# DriverModuleWing.net
KiCad netlist of a schematic drawn in EAGLE
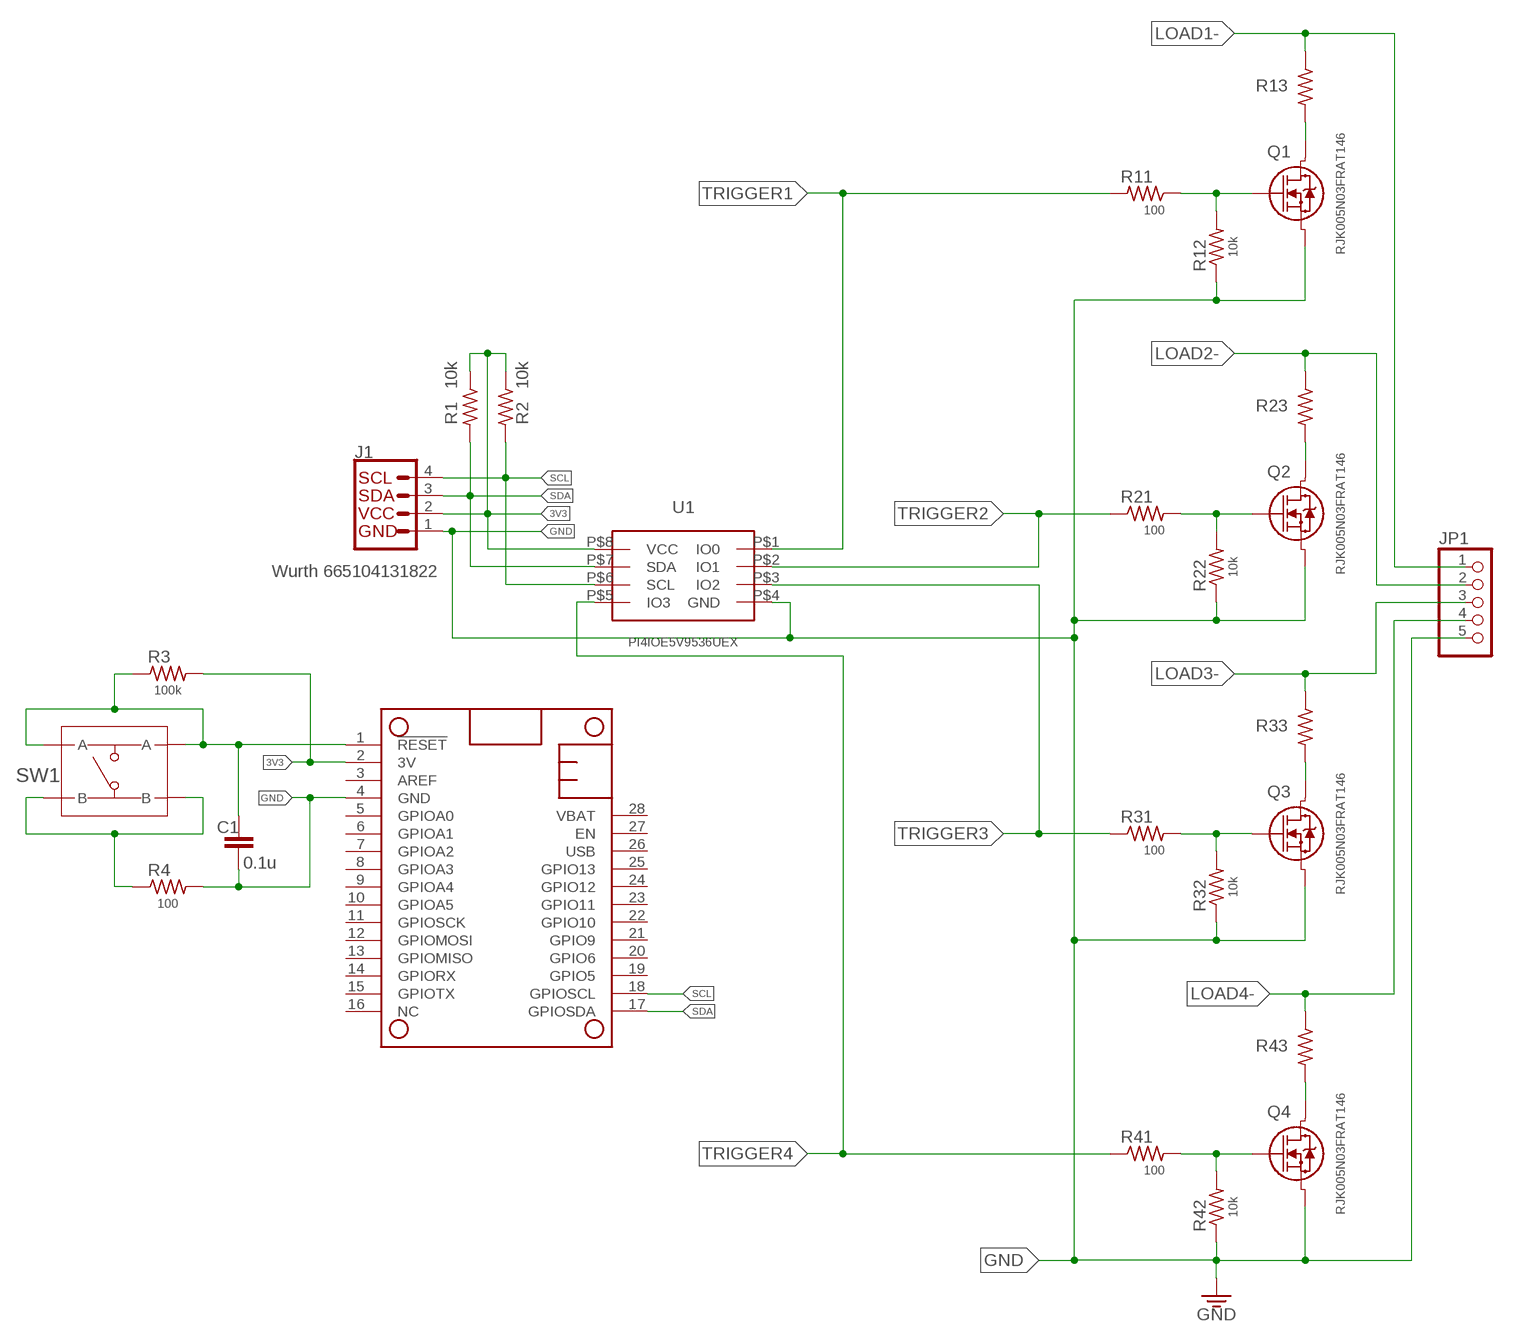
[diagram p0: schematic, sheet 1]

(export (version "E")
  (design (tool "Eeschema 10.0.6"))
  (components
    (comp (ref "C1")
      (value "0.1u")
      (footprint "eagle-import:SMD-0805")
      (libsource (lib "eagle-import") (part "C-SMD-0805"))
    )
    (comp (ref "J1")
      (value "Wurth 665104131822")
      (footprint "eagle-import:1X04_1MM_RA")
      (libsource (lib "eagle-import") (part "QWIIC_CONNECTORJS-1MM"))
    )
    (comp (ref "JP1")
      (value "HEADER-1X576MIL")
      (footprint "eagle-import:1X05_ROUND_76")
      (libsource (lib "eagle-import") (part "HEADER-1X576MIL"))
    )
    (comp (ref "MS1")
      (value "FEATHERWING_NODIM")
      (footprint "eagle-import:FEATHERWING_DIM")
      (libsource (lib "eagle-import") (part "FEATHERWING_NODIM"))
    )
    (comp (ref "Q1")
      (value "RJK005N03FRAT146")
      (footprint "eagle-import:TRANS_RHK003N_ROM-M")
      (fields (field (name "COPYRIGHT") "Copyright (C) 2022 Ultra Librarian. All rights reserved."))
      (libsource (lib "eagle-import") (part "RJK005N03FRAT146TRANS_RHK003N_ROM-M"))
    )
    (comp (ref "Q2")
      (value "RJK005N03FRAT146")
      (footprint "eagle-import:TRANS_RHK003N_ROM-M")
      (fields (field (name "COPYRIGHT") "Copyright (C) 2022 Ultra Librarian. All rights reserved."))
      (libsource (lib "eagle-import") (part "RJK005N03FRAT146TRANS_RHK003N_ROM-M"))
    )
    (comp (ref "Q3")
      (value "RJK005N03FRAT146")
      (footprint "eagle-import:TRANS_RHK003N_ROM-M")
      (fields (field (name "COPYRIGHT") "Copyright (C) 2022 Ultra Librarian. All rights reserved."))
      (libsource (lib "eagle-import") (part "RJK005N03FRAT146TRANS_RHK003N_ROM-M"))
    )
    (comp (ref "Q4")
      (value "RJK005N03FRAT146")
      (footprint "eagle-import:TRANS_RHK003N_ROM-M")
      (fields (field (name "COPYRIGHT") "Copyright (C) 2022 Ultra Librarian. All rights reserved."))
      (libsource (lib "eagle-import") (part "RJK005N03FRAT146TRANS_RHK003N_ROM-M"))
    )
    (comp (ref "R1")
      (value "10k")
      (footprint "eagle-import:R0603")
      (libsource (lib "eagle-import") (part "R-US_R0603"))
    )
    (comp (ref "R2")
      (value "10k")
      (footprint "eagle-import:R0603")
      (libsource (lib "eagle-import") (part "R-US_R0603"))
    )
    (comp (ref "R3")
      (value "100k")
      (footprint "eagle-import:R0603")
      (libsource (lib "eagle-import") (part "R-US_R0603"))
    )
    (comp (ref "R4")
      (value "100")
      (footprint "eagle-import:R0603")
      (libsource (lib "eagle-import") (part "R-US_R0603"))
    )
    (comp (ref "R11")
      (value "100")
      (footprint "eagle-import:R0603")
      (libsource (lib "eagle-import") (part "R-US_R0603"))
    )
    (comp (ref "R12")
      (value "10k")
      (footprint "eagle-import:R0603")
      (libsource (lib "eagle-import") (part "R-US_R0603"))
    )
    (comp (ref "R13")
      (value "R-US_R1206")
      (footprint "eagle-import:R1206")
      (libsource (lib "eagle-import") (part "R-US_R1206"))
    )
    (comp (ref "R21")
      (value "100")
      (footprint "eagle-import:R0603")
      (libsource (lib "eagle-import") (part "R-US_R0603"))
    )
    (comp (ref "R22")
      (value "10k")
      (footprint "eagle-import:R0603")
      (libsource (lib "eagle-import") (part "R-US_R0603"))
    )
    (comp (ref "R23")
      (value "R-US_R1206")
      (footprint "eagle-import:R1206")
      (libsource (lib "eagle-import") (part "R-US_R1206"))
    )
    (comp (ref "R31")
      (value "100")
      (footprint "eagle-import:R0603")
      (libsource (lib "eagle-import") (part "R-US_R0603"))
    )
    (comp (ref "R32")
      (value "10k")
      (footprint "eagle-import:R0603")
      (libsource (lib "eagle-import") (part "R-US_R0603"))
    )
    (comp (ref "R33")
      (value "R-US_R1206")
      (footprint "eagle-import:R1206")
      (libsource (lib "eagle-import") (part "R-US_R1206"))
    )
    (comp (ref "R41")
      (value "100")
      (footprint "eagle-import:R0603")
      (libsource (lib "eagle-import") (part "R-US_R0603"))
    )
    (comp (ref "R42")
      (value "10k")
      (footprint "eagle-import:R0603")
      (libsource (lib "eagle-import") (part "R-US_R0603"))
    )
    (comp (ref "R43")
      (value "R-US_R1206")
      (footprint "eagle-import:R1206")
      (libsource (lib "eagle-import") (part "R-US_R1206"))
    )
    (comp (ref "SW1")
      (value "PTS645SK43SMTR92LFS-PTS647-4.5")
      (footprint "eagle-import:SWITCH_CK_PTS647SN38SMTR2LFS")
      (libsource (lib "eagle-import") (part "PTS645SK43SMTR92LFS-PTS647-4.5"))
    )
    (comp (ref "U1")
      (value "PI4IOE5V9536UEX")
      (footprint "eagle-import:MSOP-8")
      (libsource (lib "eagle-import") (part "PI4IOE5V9536-UEX"))
    )
  )
  (nets
    (net (code "1") (name "/USB") (class "Default")
      (node (ref "MS1") (pin "26") (pinfunction "USB_26") (pintype "power_in"))
    )
    (net (code "2") (name "/VBAT") (class "Default")
      (node (ref "MS1") (pin "28") (pinfunction "VBAT_28") (pintype "power_in"))
    )
    (net (code "3") (name "3V3") (class "Default")
      (node (ref "J1") (pin "2") (pinfunction "VCC_2") (pintype "power_in"))
      (node (ref "MS1") (pin "2") (pinfunction "3V_2") (pintype "power_in"))
      (node (ref "R1") (pin "1") (pinfunction "1_1") (pintype "passive"))
      (node (ref "R2") (pin "1") (pinfunction "1_1") (pintype "passive"))
      (node (ref "R3") (pin "2") (pinfunction "2_2") (pintype "passive"))
      (node (ref "U1") (pin "P$8") (pinfunction "VCC_P$8") (pintype "bidirectional"))
    )
    (net (code "4") (name "GND") (class "Default")
      (node (ref "C1") (pin "P$2") (pinfunction "2_P$2") (pintype "passive"))
      (node (ref "J1") (pin "1") (pinfunction "GND_1") (pintype "power_in"))
      (node (ref "JP1") (pin "5") (pinfunction "5_5") (pintype "passive"))
      (node (ref "MS1") (pin "4") (pinfunction "GND_4") (pintype "power_in"))
      (node (ref "Q1") (pin "3") (pinfunction "3_3") (pintype "passive"))
      (node (ref "Q2") (pin "3") (pinfunction "3_3") (pintype "passive"))
      (node (ref "Q3") (pin "3") (pinfunction "3_3") (pintype "passive"))
      (node (ref "Q4") (pin "3") (pinfunction "3_3") (pintype "passive"))
      (node (ref "R12") (pin "1") (pinfunction "1_1") (pintype "passive"))
      (node (ref "R22") (pin "1") (pinfunction "1_1") (pintype "passive"))
      (node (ref "R32") (pin "1") (pinfunction "1_1") (pintype "passive"))
      (node (ref "R4") (pin "2") (pinfunction "2_2") (pintype "passive"))
      (node (ref "R42") (pin "1") (pinfunction "1_1") (pintype "passive"))
      (node (ref "U1") (pin "P$4") (pinfunction "GND_P$4") (pintype "bidirectional"))
    )
    (net (code "5") (name "LOAD1-") (class "Default")
      (node (ref "JP1") (pin "1") (pinfunction "1_1") (pintype "passive"))
      (node (ref "R13") (pin "1") (pinfunction "1_1") (pintype "passive"))
    )
    (net (code "6") (name "LOAD2-") (class "Default")
      (node (ref "JP1") (pin "2") (pinfunction "2_2") (pintype "passive"))
      (node (ref "R23") (pin "1") (pinfunction "1_1") (pintype "passive"))
    )
    (net (code "7") (name "LOAD3-") (class "Default")
      (node (ref "JP1") (pin "3") (pinfunction "3_3") (pintype "passive"))
      (node (ref "R33") (pin "1") (pinfunction "1_1") (pintype "passive"))
    )
    (net (code "8") (name "LOAD4-") (class "Default")
      (node (ref "JP1") (pin "4") (pinfunction "4_4") (pintype "passive"))
      (node (ref "R43") (pin "1") (pinfunction "1_1") (pintype "passive"))
    )
    (net (code "9") (name "Net-(C1-1)") (class "Default")
      (node (ref "C1") (pin "P$1") (pinfunction "1_P$1") (pintype "passive"))
      (node (ref "MS1") (pin "1") (pinfunction "~{RESET}_1") (pintype "input"))
      (node (ref "R3") (pin "1") (pinfunction "1_1") (pintype "passive"))
      (node (ref "SW1") (pin "1") (pinfunction "A_1") (pintype "passive"))
      (node (ref "SW1") (pin "2") (pinfunction "A_2") (pintype "passive"))
    )
    (net (code "10") (name "Net-(Q1-1)") (class "Default")
      (node (ref "Q1") (pin "2") (pinfunction "1_2") (pintype "passive"))
      (node (ref "R11") (pin "1") (pinfunction "1_1") (pintype "passive"))
      (node (ref "R12") (pin "2") (pinfunction "2_2") (pintype "passive"))
    )
    (net (code "11") (name "Net-(Q1-2)") (class "Default")
      (node (ref "Q1") (pin "1") (pinfunction "2_1") (pintype "passive"))
      (node (ref "R13") (pin "2") (pinfunction "2_2") (pintype "passive"))
    )
    (net (code "12") (name "Net-(Q2-1)") (class "Default")
      (node (ref "Q2") (pin "2") (pinfunction "1_2") (pintype "passive"))
      (node (ref "R21") (pin "2") (pinfunction "2_2") (pintype "passive"))
      (node (ref "R22") (pin "2") (pinfunction "2_2") (pintype "passive"))
    )
    (net (code "13") (name "Net-(Q2-2)") (class "Default")
      (node (ref "Q2") (pin "1") (pinfunction "2_1") (pintype "passive"))
      (node (ref "R23") (pin "2") (pinfunction "2_2") (pintype "passive"))
    )
    (net (code "14") (name "Net-(Q3-1)") (class "Default")
      (node (ref "Q3") (pin "2") (pinfunction "1_2") (pintype "passive"))
      (node (ref "R31") (pin "2") (pinfunction "2_2") (pintype "passive"))
      (node (ref "R32") (pin "2") (pinfunction "2_2") (pintype "passive"))
    )
    (net (code "15") (name "Net-(Q3-2)") (class "Default")
      (node (ref "Q3") (pin "1") (pinfunction "2_1") (pintype "passive"))
      (node (ref "R33") (pin "2") (pinfunction "2_2") (pintype "passive"))
    )
    (net (code "16") (name "Net-(Q4-1)") (class "Default")
      (node (ref "Q4") (pin "2") (pinfunction "1_2") (pintype "passive"))
      (node (ref "R41") (pin "2") (pinfunction "2_2") (pintype "passive"))
      (node (ref "R42") (pin "2") (pinfunction "2_2") (pintype "passive"))
    )
    (net (code "17") (name "Net-(Q4-2)") (class "Default")
      (node (ref "Q4") (pin "1") (pinfunction "2_1") (pintype "passive"))
      (node (ref "R43") (pin "2") (pinfunction "2_2") (pintype "passive"))
    )
    (net (code "18") (name "Net-(R4-Pad1)") (class "Default")
      (node (ref "R4") (pin "1") (pinfunction "1_1") (pintype "passive"))
      (node (ref "SW1") (pin "3") (pinfunction "B_3") (pintype "passive"))
      (node (ref "SW1") (pin "4") (pinfunction "B_4") (pintype "passive"))
    )
    (net (code "19") (name "SCL") (class "Default")
      (node (ref "J1") (pin "4") (pinfunction "SCL_4") (pintype "passive"))
      (node (ref "MS1") (pin "18") (pinfunction "GPIOSCL_18") (pintype "bidirectional"))
      (node (ref "R2") (pin "2") (pinfunction "2_2") (pintype "passive"))
      (node (ref "U1") (pin "P$6") (pinfunction "SCL_P$6") (pintype "bidirectional"))
    )
    (net (code "20") (name "SDA") (class "Default")
      (node (ref "J1") (pin "3") (pinfunction "SDA_3") (pintype "passive"))
      (node (ref "MS1") (pin "17") (pinfunction "GPIOSDA_17") (pintype "bidirectional"))
      (node (ref "R1") (pin "2") (pinfunction "2_2") (pintype "passive"))
      (node (ref "U1") (pin "P$7") (pinfunction "SDA_P$7") (pintype "bidirectional"))
    )
    (net (code "21") (name "TRIGGER1") (class "Default")
      (node (ref "R11") (pin "2") (pinfunction "2_2") (pintype "passive"))
      (node (ref "U1") (pin "P$1") (pinfunction "IO0_P$1") (pintype "bidirectional"))
    )
    (net (code "22") (name "TRIGGER2") (class "Default")
      (node (ref "R21") (pin "1") (pinfunction "1_1") (pintype "passive"))
      (node (ref "U1") (pin "P$2") (pinfunction "IO1_P$2") (pintype "bidirectional"))
    )
    (net (code "23") (name "TRIGGER3") (class "Default")
      (node (ref "R31") (pin "1") (pinfunction "1_1") (pintype "passive"))
      (node (ref "U1") (pin "P$3") (pinfunction "IO2_P$3") (pintype "bidirectional"))
    )
    (net (code "24") (name "TRIGGER4") (class "Default")
      (node (ref "R41") (pin "1") (pinfunction "1_1") (pintype "passive"))
      (node (ref "U1") (pin "P$5") (pinfunction "IO3_P$5") (pintype "bidirectional"))
    )
    (net (code "25") (name "unconnected-(MS1-AREF-Pad3)") (class "Default")
      (node (ref "MS1") (pin "3") (pinfunction "AREF_3") (pintype "passive"))
    )
    (net (code "26") (name "unconnected-(MS1-EN-Pad27)") (class "Default")
      (node (ref "MS1") (pin "27") (pinfunction "EN_27") (pintype "passive"))
    )
    (net (code "27") (name "unconnected-(MS1-GPIO5-Pad19)") (class "Default")
      (node (ref "MS1") (pin "19") (pinfunction "GPIO5_19") (pintype "bidirectional"))
    )
    (net (code "28") (name "unconnected-(MS1-GPIO6-Pad20)") (class "Default")
      (node (ref "MS1") (pin "20") (pinfunction "GPIO6_20") (pintype "bidirectional"))
    )
    (net (code "29") (name "unconnected-(MS1-GPIO9-Pad21)") (class "Default")
      (node (ref "MS1") (pin "21") (pinfunction "GPIO9_21") (pintype "bidirectional"))
    )
    (net (code "30") (name "unconnected-(MS1-GPIO10-Pad22)") (class "Default")
      (node (ref "MS1") (pin "22") (pinfunction "GPIO10_22") (pintype "bidirectional"))
    )
    (net (code "31") (name "unconnected-(MS1-GPIO11-Pad23)") (class "Default")
      (node (ref "MS1") (pin "23") (pinfunction "GPIO11_23") (pintype "bidirectional"))
    )
    (net (code "32") (name "unconnected-(MS1-GPIO12-Pad24)") (class "Default")
      (node (ref "MS1") (pin "24") (pinfunction "GPIO12_24") (pintype "bidirectional"))
    )
    (net (code "33") (name "unconnected-(MS1-GPIO13-Pad25)") (class "Default")
      (node (ref "MS1") (pin "25") (pinfunction "GPIO13_25") (pintype "bidirectional"))
    )
    (net (code "34") (name "unconnected-(MS1-GPIOA0-Pad5)") (class "Default")
      (node (ref "MS1") (pin "5") (pinfunction "GPIOA0_5") (pintype "bidirectional"))
    )
    (net (code "35") (name "unconnected-(MS1-GPIOA1-Pad6)") (class "Default")
      (node (ref "MS1") (pin "6") (pinfunction "GPIOA1_6") (pintype "bidirectional"))
    )
    (net (code "36") (name "unconnected-(MS1-GPIOA2-Pad7)") (class "Default")
      (node (ref "MS1") (pin "7") (pinfunction "GPIOA2_7") (pintype "bidirectional"))
    )
    (net (code "37") (name "unconnected-(MS1-GPIOA3-Pad8)") (class "Default")
      (node (ref "MS1") (pin "8") (pinfunction "GPIOA3_8") (pintype "bidirectional"))
    )
    (net (code "38") (name "unconnected-(MS1-GPIOA4-Pad9)") (class "Default")
      (node (ref "MS1") (pin "9") (pinfunction "GPIOA4_9") (pintype "bidirectional"))
    )
    (net (code "39") (name "unconnected-(MS1-GPIOA5-Pad10)") (class "Default")
      (node (ref "MS1") (pin "10") (pinfunction "GPIOA5_10") (pintype "bidirectional"))
    )
    (net (code "40") (name "unconnected-(MS1-GPIOMISO-Pad13)") (class "Default")
      (node (ref "MS1") (pin "13") (pinfunction "GPIOMISO_13") (pintype "bidirectional"))
    )
    (net (code "41") (name "unconnected-(MS1-GPIOMOSI-Pad12)") (class "Default")
      (node (ref "MS1") (pin "12") (pinfunction "GPIOMOSI_12") (pintype "bidirectional"))
    )
    (net (code "42") (name "unconnected-(MS1-GPIORX-Pad14)") (class "Default")
      (node (ref "MS1") (pin "14") (pinfunction "GPIORX_14") (pintype "bidirectional"))
    )
    (net (code "43") (name "unconnected-(MS1-GPIOSCK-Pad11)") (class "Default")
      (node (ref "MS1") (pin "11") (pinfunction "GPIOSCK_11") (pintype "bidirectional"))
    )
    (net (code "44") (name "unconnected-(MS1-GPIOTX-Pad15)") (class "Default")
      (node (ref "MS1") (pin "15") (pinfunction "GPIOTX_15") (pintype "bidirectional"))
    )
    (net (code "45") (name "unconnected-(MS1-NC-Pad16)") (class "Default")
      (node (ref "MS1") (pin "16") (pinfunction "NC_16") (pintype "passive"))
    )
  )
)
